# SSR_v0_9b.net
KiCad netlist of a schematic drawn in EAGLE
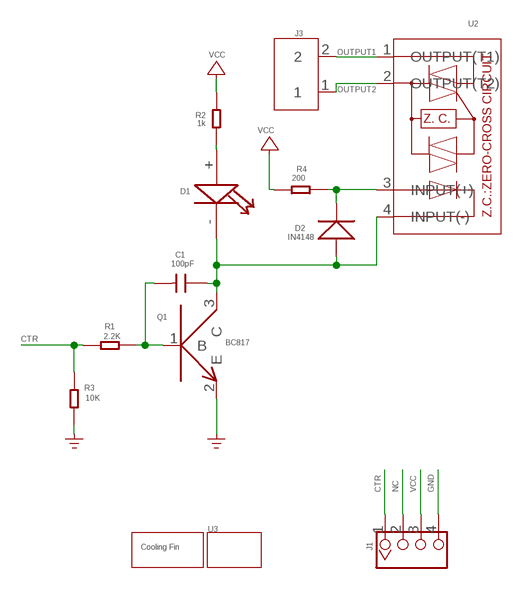
[diagram p0: schematic, sheet 1]

(export (version "E")
  (design (tool "Eeschema 10.0.6"))
  (components
    (comp (ref "C1")
      (value "100pF")
      (footprint "eagle-import:0603")
      (libsource (lib "eagle-import") (part "C-0603"))
    )
    (comp (ref "D1")
      (value "LED0805")
      (footprint "eagle-import:LED0805")
      (libsource (lib "eagle-import") (part "LED0805"))
    )
    (comp (ref "D2")
      (value "IN4148")
      (footprint "eagle-import:DO-35-SMD")
      (libsource (lib "eagle-import") (part "D1N4148-SMD"))
    )
    (comp (ref "J1")
      (value "TWIG-4P-2.0-2.0")
      (footprint "eagle-import:4P-2.0")
      (libsource (lib "eagle-import") (part "TWIG-4P-2.0-2.0"))
    )
    (comp (ref "J3")
      (value "SCREW-TERMINAL-2P5.0")
      (footprint "eagle-import:2P-5.0")
      (libsource (lib "eagle-import") (part "SCREW-TERMINAL-2P5.0"))
    )
    (comp (ref "Q1")
      (value "NPN_9013")
      (footprint "eagle-import:SOT23")
      (libsource (lib "eagle-import") (part "NPN_9013"))
    )
    (comp (ref "R1")
      (value "2.2K")
      (footprint "eagle-import:0603")
      (libsource (lib "eagle-import") (part "R-0603"))
    )
    (comp (ref "R2")
      (value "1k")
      (footprint "eagle-import:0603")
      (libsource (lib "eagle-import") (part "R-0603"))
    )
    (comp (ref "R3")
      (value "10K")
      (footprint "eagle-import:0603")
      (libsource (lib "eagle-import") (part "R-0603"))
    )
    (comp (ref "R4")
      (value "200")
      (footprint "eagle-import:0603")
      (libsource (lib "eagle-import") (part "R-0603"))
    )
    (comp (ref "U1")
      (value "SILK-COOLING-FIN")
      (footprint "eagle-import:COOLING-FIN-30X25")
      (libsource (lib "eagle-import") (part "SILK-COOLING-FIN"))
    )
    (comp (ref "U2")
      (value "RELAY-S208T02")
      (footprint "eagle-import:4P-23X4X16H")
      (libsource (lib "eagle-import") (part "RELAY-S208T02"))
    )
    (comp (ref "U3")
      (value "TWIG-2X2U")
      (footprint "eagle-import:2X2U-DIM-W_-DRILL")
      (libsource (lib "eagle-import") (part "TWIG-2X2U"))
    )
  )
  (nets
    (net (code "1") (name "/CTR") (class "Default")
      (node (ref "J1") (pin "1") (pinfunction "1_1") (pintype "bidirectional"))
      (node (ref "R1") (pin "1") (pinfunction "1_1") (pintype "passive"))
      (node (ref "R3") (pin "2") (pinfunction "2_2") (pintype "passive"))
    )
    (net (code "2") (name "/NC") (class "Default")
      (node (ref "J1") (pin "2") (pinfunction "2_2") (pintype "bidirectional"))
    )
    (net (code "3") (name "/OUTPUT1") (class "Default")
      (node (ref "J3") (pin "2") (pinfunction "2_2") (pintype "bidirectional"))
      (node (ref "U2") (pin "1") (pinfunction "OUTPUT(T1)_1") (pintype "bidirectional"))
    )
    (net (code "4") (name "/OUTPUT2") (class "Default")
      (node (ref "J3") (pin "1") (pinfunction "1_1") (pintype "bidirectional"))
      (node (ref "U2") (pin "2") (pinfunction "OUTPUT(T2)_2") (pintype "bidirectional"))
    )
    (net (code "5") (name "GND_POWER") (class "Default")
      (node (ref "J1") (pin "4") (pinfunction "4_4") (pintype "bidirectional"))
      (node (ref "Q1") (pin "2") (pinfunction "E_2") (pintype "bidirectional"))
      (node (ref "R3") (pin "1") (pinfunction "1_1") (pintype "passive"))
    )
    (net (code "6") (name "Net-(D1-Pad+)") (class "Default")
      (node (ref "D1") (pin "+") (pinfunction "+_+") (pintype "bidirectional"))
      (node (ref "R2") (pin "1") (pinfunction "1_1") (pintype "passive"))
    )
    (net (code "7") (name "Net-(D2-+)") (class "Default")
      (node (ref "C1") (pin "1") (pinfunction "1_1") (pintype "passive"))
      (node (ref "D1") (pin "-") (pinfunction "-_-") (pintype "bidirectional"))
      (node (ref "D2") (pin "A") (pinfunction "+_A") (pintype "passive"))
      (node (ref "Q1") (pin "3") (pinfunction "C_3") (pintype "bidirectional"))
      (node (ref "U2") (pin "4") (pinfunction "INPUT(-)_4") (pintype "bidirectional"))
    )
    (net (code "8") (name "Net-(D2--)") (class "Default")
      (node (ref "D2") (pin "C") (pinfunction "-_C") (pintype "passive"))
      (node (ref "R4") (pin "2") (pinfunction "2_2") (pintype "passive"))
      (node (ref "U2") (pin "3") (pinfunction "INPUT(+)_3") (pintype "bidirectional"))
    )
    (net (code "9") (name "Net-(Q1-B)") (class "Default")
      (node (ref "C1") (pin "2") (pinfunction "2_2") (pintype "passive"))
      (node (ref "Q1") (pin "1") (pinfunction "B_1") (pintype "bidirectional"))
      (node (ref "R1") (pin "2") (pinfunction "2_2") (pintype "passive"))
    )
    (net (code "10") (name "POWER_ARROW") (class "Default")
      (node (ref "J1") (pin "3") (pinfunction "3_3") (pintype "bidirectional"))
      (node (ref "R2") (pin "2") (pinfunction "2_2") (pintype "passive"))
      (node (ref "R4") (pin "1") (pinfunction "1_1") (pintype "passive"))
    )
  )
)
